# carrier.net
KiCad netlist of a schematic drawn in Altium Designer
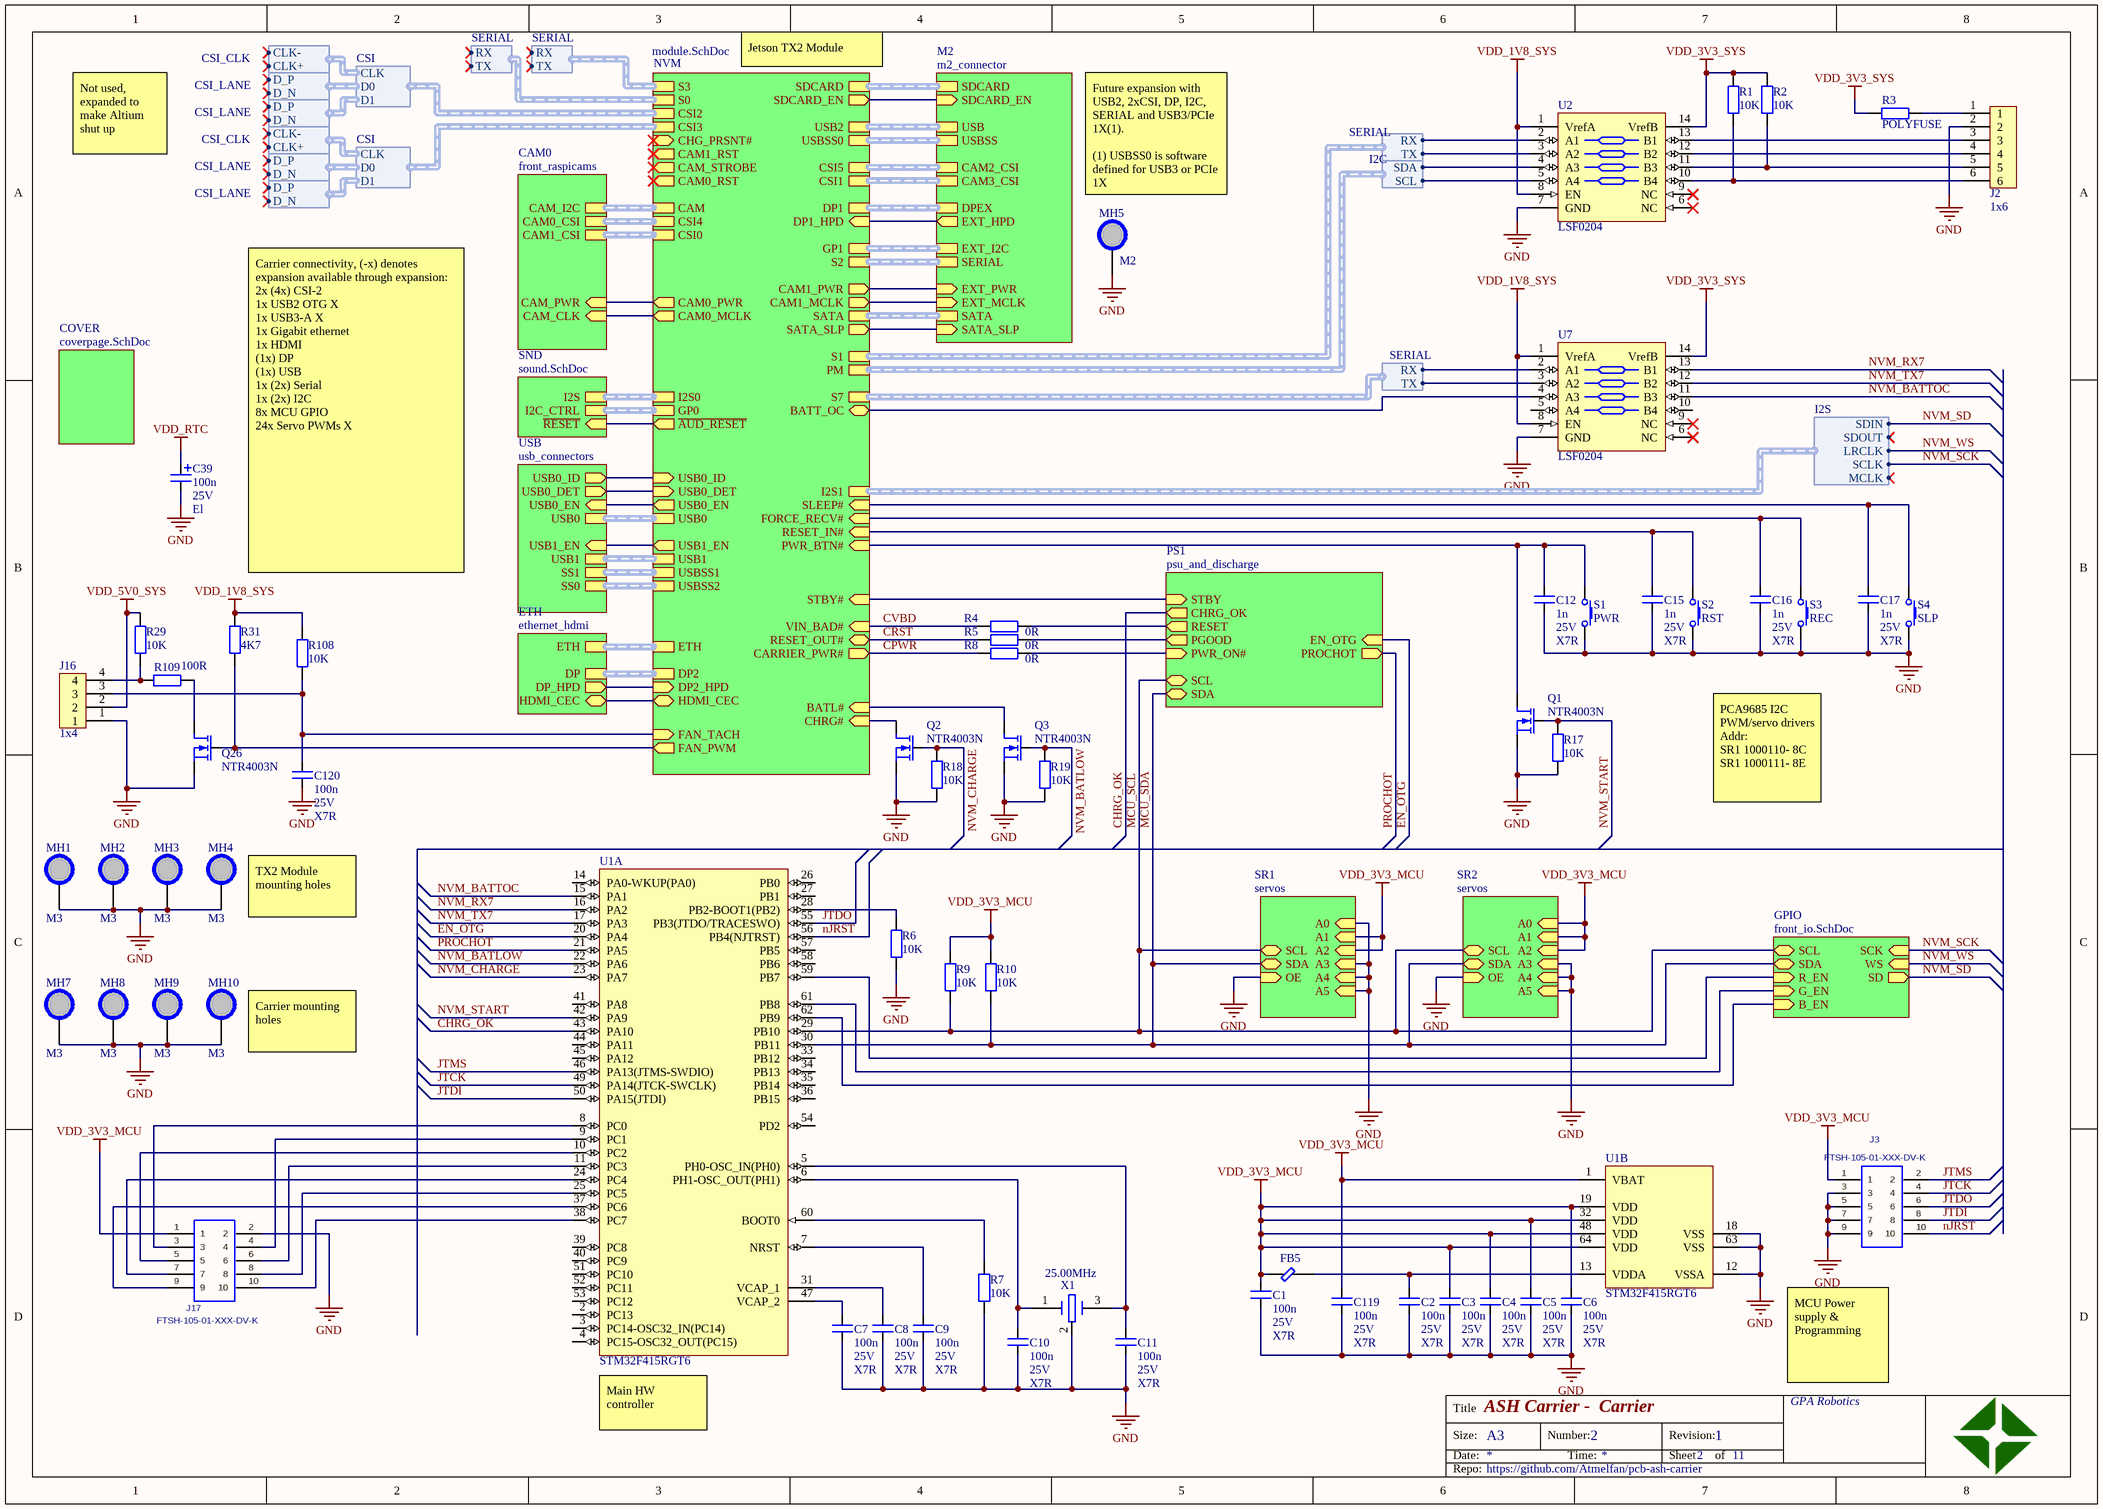
[diagram p0: carrier.SchDoc]

(export (version "E")
  (design (tool "Eeschema 10.0.6"))
  (components
    (comp (ref "C1")
      (value "100n")
      (footprint "C1005[0402]")
      (description "Capacitor")
      (fields (field (name "VOLTAGE") "25V") (field (name "TYPE") "X7R") (field (name "Comment") "cap"))
      (libsource (lib "gpa_passives") (part "cap"))
    )
    (comp (ref "C2")
      (value "100n")
      (footprint "C1005[0402]")
      (description "Capacitor")
      (fields (field (name "VOLTAGE") "25V") (field (name "TYPE") "X7R") (field (name "Comment") "cap"))
      (libsource (lib "gpa_passives") (part "cap"))
    )
    (comp (ref "C3")
      (value "100n")
      (footprint "C1005[0402]")
      (description "Capacitor")
      (fields (field (name "VOLTAGE") "25V") (field (name "TYPE") "X7R") (field (name "Comment") "cap"))
      (libsource (lib "gpa_passives") (part "cap"))
    )
    (comp (ref "C4")
      (value "100n")
      (footprint "C1005[0402]")
      (description "Capacitor")
      (fields (field (name "VOLTAGE") "25V") (field (name "TYPE") "X7R") (field (name "Comment") "cap"))
      (libsource (lib "gpa_passives") (part "cap"))
    )
    (comp (ref "C5")
      (value "100n")
      (footprint "C1005[0402]")
      (description "Capacitor")
      (fields (field (name "VOLTAGE") "25V") (field (name "TYPE") "X7R") (field (name "Comment") "cap"))
      (libsource (lib "gpa_passives") (part "cap"))
    )
    (comp (ref "C6")
      (value "100n")
      (footprint "C1005[0402]")
      (description "Capacitor")
      (fields (field (name "VOLTAGE") "25V") (field (name "TYPE") "X7R") (field (name "Comment") "cap"))
      (libsource (lib "gpa_passives") (part "cap"))
    )
    (comp (ref "C7")
      (value "100n")
      (footprint "C1005[0402]")
      (description "Capacitor")
      (fields (field (name "VOLTAGE") "25V") (field (name "TYPE") "X7R") (field (name "Comment") "cap"))
      (libsource (lib "gpa_passives") (part "cap"))
    )
    (comp (ref "C8")
      (value "100n")
      (footprint "C1005[0402]")
      (description "Capacitor")
      (fields (field (name "VOLTAGE") "25V") (field (name "TYPE") "X7R") (field (name "Comment") "cap"))
      (libsource (lib "gpa_passives") (part "cap"))
    )
    (comp (ref "C9")
      (value "100n")
      (footprint "C1005[0402]")
      (description "Capacitor")
      (fields (field (name "VOLTAGE") "25V") (field (name "TYPE") "X7R") (field (name "Comment") "cap"))
      (libsource (lib "gpa_passives") (part "cap"))
    )
    (comp (ref "C10")
      (value "100n")
      (footprint "C1005[0402]")
      (description "Capacitor")
      (fields (field (name "VOLTAGE") "25V") (field (name "TYPE") "X7R") (field (name "Comment") "cap"))
      (libsource (lib "gpa_passives") (part "cap"))
    )
    (comp (ref "C11")
      (value "100n")
      (footprint "C1005[0402]")
      (description "Capacitor")
      (fields (field (name "VOLTAGE") "25V") (field (name "TYPE") "X7R") (field (name "Comment") "cap"))
      (libsource (lib "gpa_passives") (part "cap"))
    )
    (comp (ref "C12")
      (value "1n")
      (footprint "C1005[0402]")
      (description "Capacitor")
      (fields (field (name "VOLTAGE") "25V") (field (name "TYPE") "X7R") (field (name "Comment") "cap"))
      (libsource (lib "gpa_passives") (part "cap"))
    )
    (comp (ref "C15")
      (value "1n")
      (footprint "C1005[0402]")
      (description "Capacitor")
      (fields (field (name "VOLTAGE") "25V") (field (name "TYPE") "X7R") (field (name "Comment") "cap"))
      (libsource (lib "gpa_passives") (part "cap"))
    )
    (comp (ref "C16")
      (value "1n")
      (footprint "C1005[0402]")
      (description "Capacitor")
      (fields (field (name "VOLTAGE") "25V") (field (name "TYPE") "X7R") (field (name "Comment") "cap"))
      (libsource (lib "gpa_passives") (part "cap"))
    )
    (comp (ref "C17")
      (value "1n")
      (footprint "C1005[0402]")
      (description "Capacitor")
      (fields (field (name "VOLTAGE") "25V") (field (name "TYPE") "X7R") (field (name "Comment") "cap"))
      (libsource (lib "gpa_passives") (part "cap"))
    )
    (comp (ref "C39")
      (value "100n")
      (footprint "SC_DSK-3R3H224U-HL")
      (description "Polarized capacitor")
      (fields (field (name "VOLTAGE") "25V") (field (name "TYPE") "El") (field (name "Comment") "pcap"))
      (libsource (lib "gpa_passives") (part "pcap"))
    )
    (comp (ref "C119")
      (value "100n")
      (footprint "C1005[0402]")
      (description "Capacitor")
      (fields (field (name "VOLTAGE") "25V") (field (name "TYPE") "X7R") (field (name "Comment") "cap"))
      (libsource (lib "gpa_passives") (part "cap"))
    )
    (comp (ref "C120")
      (value "100n")
      (footprint "C1005[0402]")
      (description "Capacitor")
      (fields (field (name "VOLTAGE") "25V") (field (name "TYPE") "X7R") (field (name "Comment") "cap"))
      (libsource (lib "gpa_passives") (part "cap"))
    )
    (comp (ref "FB5")
      (value "2506036007Y3")
      (footprint "FBC1608X07N")
      (description "Ferrite bead")
      (libsource (lib "gpa_passives") (part "ferrite_bead"))
    )
    (comp (ref "J2")
      (value "1x6")
      (footprint "hdr_100mil_1x6")
      (libsource (lib "gpa_connectors") (part "header_1x6"))
    )
    (comp (ref "J3")
      (value "FTSH-105-01-XXX-DV-K")
      (footprint "FTSH-105-01-XXX-DV-K")
      (description "TERMINAL STRIP, .050\"(1.27mm) PITCH, 10 PINS, KEYED")
      (fields (field (name "MANUFACTURER") "SAMTEC") (field (name "CREATED") "November 30, 2016 - Wendy Xin"))
      (libsource (lib "FTSH-105-01-XXX-DV-K") (part "FTSH-105-01-XXX-DV-K"))
    )
    (comp (ref "J16")
      (value "1x4")
      (footprint "molex_picoblade_1x4")
      (libsource (lib "gpa_connectors") (part "header_1x4"))
    )
    (comp (ref "J17")
      (value "FTSH-105-01-XXX-DV-K")
      (footprint "FTSH-105-01-XXX-DV-K")
      (description "TERMINAL STRIP, .050\"(1.27mm) PITCH, 10 PINS, KEYED")
      (fields (field (name "MANUFACTURER") "SAMTEC") (field (name "CREATED") "November 30, 2016 - Wendy Xin"))
      (libsource (lib "FTSH-105-01-XXX-DV-K") (part "FTSH-105-01-XXX-DV-K"))
    )
    (comp (ref "MH1")
      (value "M3")
      (footprint "m3_pan_tight_round")
      (libsource (lib "gpa_mounting") (part "mounting_hole"))
    )
    (comp (ref "MH2")
      (value "M3")
      (footprint "m3_pan_tight_round")
      (libsource (lib "gpa_mounting") (part "mounting_hole"))
    )
    (comp (ref "MH3")
      (value "M3")
      (footprint "m3_pan_tight_round")
      (libsource (lib "gpa_mounting") (part "mounting_hole"))
    )
    (comp (ref "MH4")
      (value "M3")
      (footprint "m3_pan_tight_round")
      (libsource (lib "gpa_mounting") (part "mounting_hole"))
    )
    (comp (ref "MH5")
      (value "M2")
      (footprint "m2_pan_tight_round")
      (libsource (lib "gpa_mounting") (part "mounting_hole"))
    )
    (comp (ref "MH7")
      (value "M3")
      (footprint "m3_pan_tight_round")
      (libsource (lib "gpa_mounting") (part "mounting_hole"))
    )
    (comp (ref "MH8")
      (value "M3")
      (footprint "m3_pan_tight_round")
      (libsource (lib "gpa_mounting") (part "mounting_hole"))
    )
    (comp (ref "MH9")
      (value "M3")
      (footprint "m3_pan_tight_round")
      (libsource (lib "gpa_mounting") (part "mounting_hole"))
    )
    (comp (ref "MH10")
      (value "M3")
      (footprint "m3_pan_tight_round")
      (libsource (lib "gpa_mounting") (part "mounting_hole"))
    )
    (comp (ref "Q1")
      (value "NTR4003N")
      (footprint "NCH_SOT95P237X110-3N")
      (libsource (lib "gpa_actives") (part "nch_mosfet"))
    )
    (comp (ref "Q2")
      (value "NTR4003N")
      (footprint "NCH_SOT95P237X110-3N")
      (libsource (lib "gpa_actives") (part "nch_mosfet"))
    )
    (comp (ref "Q3")
      (value "NTR4003N")
      (footprint "NCH_SOT95P237X110-3N")
      (libsource (lib "gpa_actives") (part "nch_mosfet"))
    )
    (comp (ref "Q26")
      (value "NTR4003N")
      (footprint "NCH_SOT95P237X110-3N")
      (libsource (lib "gpa_actives") (part "nch_mosfet"))
    )
    (comp (ref "R1")
      (value "10K")
      (footprint "R1005[0402]")
      (description "Resistor")
      (fields (field (name "Comment") "res"))
      (libsource (lib "") (part "res_1"))
    )
    (comp (ref "R2")
      (value "10K")
      (footprint "R1005[0402]")
      (description "Resistor")
      (fields (field (name "Comment") "res"))
      (libsource (lib "") (part "res_1"))
    )
    (comp (ref "R3")
      (value "POLYFUSE")
      (footprint "R1005[0402]")
      (description "Resistor")
      (fields (field (name "Comment") "res"))
      (libsource (lib "gpa_passives") (part "res"))
    )
    (comp (ref "R4")
      (value "0R")
      (footprint "R1005[0402]")
      (description "Resistor")
      (fields (field (name "Comment") "res"))
      (libsource (lib "") (part "res_1"))
    )
    (comp (ref "R5")
      (value "0R")
      (footprint "R1005[0402]")
      (description "Resistor")
      (fields (field (name "Comment") "res"))
      (libsource (lib "") (part "res_1"))
    )
    (comp (ref "R6")
      (value "10K")
      (footprint "R1005[0402]")
      (description "Resistor")
      (fields (field (name "Comment") "res"))
      (libsource (lib "") (part "res_2"))
    )
    (comp (ref "R7")
      (value "10K")
      (footprint "R1005[0402]")
      (description "Resistor")
      (fields (field (name "Comment") "res"))
      (libsource (lib "") (part "res_2"))
    )
    (comp (ref "R8")
      (value "0R")
      (footprint "R1005[0402]")
      (description "Resistor")
      (fields (field (name "Comment") "res"))
      (libsource (lib "") (part "res_1"))
    )
    (comp (ref "R9")
      (value "10K")
      (footprint "R1005[0402]")
      (description "Resistor")
      (fields (field (name "Comment") "res"))
      (libsource (lib "") (part "res_2"))
    )
    (comp (ref "R10")
      (value "10K")
      (footprint "R1005[0402]")
      (description "Resistor")
      (fields (field (name "Comment") "res"))
      (libsource (lib "") (part "res_2"))
    )
    (comp (ref "R17")
      (value "10K")
      (footprint "R1005[0402]")
      (description "Resistor")
      (fields (field (name "Comment") "res"))
      (libsource (lib "") (part "res_2"))
    )
    (comp (ref "R18")
      (value "10K")
      (footprint "R1005[0402]")
      (description "Resistor")
      (fields (field (name "Comment") "res"))
      (libsource (lib "") (part "res_2"))
    )
    (comp (ref "R19")
      (value "10K")
      (footprint "R1005[0402]")
      (description "Resistor")
      (fields (field (name "Comment") "res"))
      (libsource (lib "") (part "res_2"))
    )
    (comp (ref "R29")
      (value "10K")
      (footprint "R1005[0402]")
      (description "Resistor")
      (fields (field (name "TOLERANCE") "5%") (field (name "Comment") "res"))
      (libsource (lib "gpa_passives") (part "res"))
    )
    (comp (ref "R31")
      (value "4K7")
      (footprint "R1005[0402]")
      (description "Resistor")
      (fields (field (name "TOLERANCE") "5%") (field (name "Comment") "res"))
      (libsource (lib "") (part "res_2"))
    )
    (comp (ref "R108")
      (value "10K")
      (footprint "R1005[0402]")
      (description "Resistor")
      (fields (field (name "TOLERANCE") "5%") (field (name "Comment") "res"))
      (libsource (lib "") (part "res_2"))
    )
    (comp (ref "R109")
      (value "100R")
      (footprint "R1005[0402]")
      (description "Resistor")
      (fields (field (name "TOLERANCE") "5%") (field (name "Comment") "res"))
      (libsource (lib "") (part "res_1"))
    )
    (comp (ref "S1")
      (value "PWR")
      (footprint "SW_6MM_TACT")
      (fields (field (name "TEXT") "PWR"))
      (libsource (lib "gpa_passives") (part "btn"))
    )
    (comp (ref "S2")
      (value "RST")
      (footprint "SW_6MM_TACT")
      (fields (field (name "TEXT") "RST"))
      (libsource (lib "gpa_passives") (part "btn"))
    )
    (comp (ref "S3")
      (value "REC")
      (footprint "SW_6MM_TACT")
      (fields (field (name "TEXT") "REC"))
      (libsource (lib "gpa_passives") (part "btn"))
    )
    (comp (ref "S4")
      (value "SLP")
      (footprint "SW_6MM_TACT")
      (fields (field (name "TEXT") "SLP"))
      (libsource (lib "gpa_passives") (part "btn"))
    )
    (comp (ref "U1")
      (value "STM32F415RGT6")
      (footprint "STM-LQFP64_N")
      (fields (field (name "MANUFACTURER") "STMicroelectronics"))
      (libsource (lib "STMicroelectronics STM32 F4") (part "STM32F415RGT6"))
    )
    (comp (ref "U2")
      (value "LSF0204")
      (footprint "TI_TSOP65P640X120-14N")
      (libsource (lib "gpa_ti") (part "lsf0204"))
    )
    (comp (ref "U7")
      (value "LSF0204")
      (footprint "TI_TSOP65P640X120-14N")
      (libsource (lib "gpa_ti") (part "lsf0204"))
    )
    (comp (ref "X1")
      (value "25.00MHz")
      (footprint "FA-238")
      (description "Crystal with shield")
      (fields (field (name "Comment") "crystal_shielded"))
      (libsource (lib "gpa_passives") (part "crystal_shielded"))
    )
  )
  (nets
    (net (code "6") (name "/BATL#") (class "Default")
      (node (ref "Q3") (pin "D") (pinfunction "D_D") (pintype "passive"))
    )
    (net (code "7") (name "/BATT_OC") (class "Default")
      (node (ref "U7") (pin "4") (pinfunction "A3_4") (pintype "bidirectional"))
    )
    (net (code "8") (name "/B_EN") (class "Default")
      (node (ref "U1") (pin "62") (pinfunction "PB9_62") (pintype "bidirectional"))
    )
    (net (code "22") (name "/CHRG#") (class "Default")
      (node (ref "Q2") (pin "D") (pinfunction "D_D") (pintype "passive"))
    )
    (net (code "23") (name "/CHRG_OK") (class "Default")
      (node (ref "U1") (pin "43") (pinfunction "PA10_43") (pintype "bidirectional"))
    )
    (net (code "24") (name "/CPWR") (class "Default")
      (node (ref "R8") (pin "1") (pinfunction "1_1") (pintype "passive"))
    )
    (net (code "25") (name "/CRST") (class "Default")
      (node (ref "R5") (pin "1") (pinfunction "1_1") (pintype "passive"))
    )
    (net (code "27") (name "/CVBD") (class "Default")
      (node (ref "R4") (pin "1") (pinfunction "1_1") (pintype "passive"))
    )
    (net (code "31") (name "/EN_OTG") (class "Default")
      (node (ref "U1") (pin "20") (pinfunction "PA4_20") (pintype "bidirectional"))
    )
    (net (code "35") (name "/FAN_PWM") (class "Default")
      (node (ref "Q26") (pin "G") (pinfunction "G_G") (pintype "passive"))
      (node (ref "R31") (pin "1") (pinfunction "1_1") (pintype "passive"))
    )
    (net (code "36") (name "/FAN_TACH") (class "Default")
      (node (ref "C120") (pin "2") (pinfunction "2_2") (pintype "passive"))
      (node (ref "J16") (pin "3") (pinfunction "3_3") (pintype "passive"))
      (node (ref "R108") (pin "1") (pinfunction "1_1") (pintype "passive"))
    )
    (net (code "37") (name "/FORCE_RECV#") (class "Default")
      (node (ref "C16") (pin "2") (pinfunction "2_2") (pintype "passive"))
      (node (ref "S3") (pin "1") (pinfunction "1_1") (pintype "passive"))
    )
    (net (code "39") (name "/G_EN") (class "Default")
      (node (ref "U1") (pin "61") (pinfunction "PB8_61") (pintype "bidirectional"))
    )
    (net (code "42") (name "/JTCK") (class "Default")
      (node (ref "J3") (pin "4") (pinfunction "4_4") (pintype "passive"))
      (node (ref "U1") (pin "49") (pinfunction "PA14(JTCK-SWCLK)_49") (pintype "bidirectional"))
    )
    (net (code "43") (name "/JTDI") (class "Default")
      (node (ref "J3") (pin "8") (pinfunction "8_8") (pintype "passive"))
      (node (ref "U1") (pin "50") (pinfunction "PA15(JTDI)_50") (pintype "bidirectional"))
    )
    (net (code "44") (name "/JTDO") (class "Default")
      (node (ref "J3") (pin "6") (pinfunction "6_6") (pintype "passive"))
      (node (ref "U1") (pin "55") (pinfunction "PB3(JTDO/TRACESWO)_55") (pintype "bidirectional"))
    )
    (net (code "45") (name "/JTMS") (class "Default")
      (node (ref "J3") (pin "2") (pinfunction "2_2") (pintype "passive"))
      (node (ref "U1") (pin "46") (pinfunction "PA13(JTMS-SWDIO)_46") (pintype "bidirectional"))
    )
    (net (code "46") (name "/MCU_SCL") (class "Default")
      (node (ref "R9") (pin "1") (pinfunction "1_1") (pintype "passive"))
      (node (ref "U1") (pin "29") (pinfunction "PB10_29") (pintype "bidirectional"))
    )
    (net (code "47") (name "/MCU_SDA") (class "Default")
      (node (ref "R10") (pin "1") (pinfunction "1_1") (pintype "passive"))
      (node (ref "U1") (pin "30") (pinfunction "PB11_30") (pintype "bidirectional"))
    )
    (net (code "48") (name "/NVM_BATLOW") (class "Default")
      (node (ref "Q3") (pin "G") (pinfunction "G_G") (pintype "passive"))
      (node (ref "R19") (pin "2") (pinfunction "2_2") (pintype "passive"))
      (node (ref "U1") (pin "22") (pinfunction "PA6_22") (pintype "bidirectional"))
    )
    (net (code "49") (name "/NVM_BATTOC") (class "Default")
      (node (ref "U1") (pin "15") (pinfunction "PA1_15") (pintype "bidirectional"))
      (node (ref "U7") (pin "11") (pinfunction "B3_11") (pintype "bidirectional"))
    )
    (net (code "50") (name "/NVM_CHARGE") (class "Default")
      (node (ref "Q2") (pin "G") (pinfunction "G_G") (pintype "passive"))
      (node (ref "R18") (pin "2") (pinfunction "2_2") (pintype "passive"))
      (node (ref "U1") (pin "23") (pinfunction "PA7_23") (pintype "bidirectional"))
    )
    (net (code "51") (name "/NVM_RX7") (class "Default")
      (node (ref "U1") (pin "16") (pinfunction "PA2_16") (pintype "bidirectional"))
      (node (ref "U7") (pin "13") (pinfunction "B1_13") (pintype "bidirectional"))
    )
    (net (code "54") (name "/NVM_START") (class "Default")
      (node (ref "Q1") (pin "G") (pinfunction "G_G") (pintype "passive"))
      (node (ref "R17") (pin "2") (pinfunction "2_2") (pintype "passive"))
      (node (ref "U1") (pin "42") (pinfunction "PA9_42") (pintype "bidirectional"))
    )
    (net (code "55") (name "/NVM_TX7") (class "Default")
      (node (ref "U1") (pin "17") (pinfunction "PA3_17") (pintype "bidirectional"))
      (node (ref "U7") (pin "12") (pinfunction "B2_12") (pintype "bidirectional"))
    )
    (net (code "57") (name "/PGOOD") (class "Default")
      (node (ref "R5") (pin "2") (pinfunction "2_2") (pintype "passive"))
    )
    (net (code "58") (name "/PROCHOT") (class "Default")
      (node (ref "U1") (pin "21") (pinfunction "PA5_21") (pintype "bidirectional"))
    )
    (net (code "59") (name "/PWR_BTN#") (class "Default")
      (node (ref "C12") (pin "2") (pinfunction "2_2") (pintype "passive"))
      (node (ref "Q1") (pin "D") (pinfunction "D_D") (pintype "passive"))
      (node (ref "S1") (pin "1") (pinfunction "1_1") (pintype "passive"))
    )
    (net (code "60") (name "/PWR_ON#") (class "Default")
      (node (ref "R8") (pin "2") (pinfunction "2_2") (pintype "passive"))
    )
    (net (code "61") (name "/RESET") (class "Default")
      (node (ref "R4") (pin "2") (pinfunction "2_2") (pintype "passive"))
    )
    (net (code "62") (name "/RESET_IN#") (class "Default")
      (node (ref "C15") (pin "2") (pinfunction "2_2") (pintype "passive"))
      (node (ref "S2") (pin "1") (pinfunction "1_1") (pintype "passive"))
    )
    (net (code "63") (name "/R_EN") (class "Default")
      (node (ref "U1") (pin "59") (pinfunction "PB7_59") (pintype "bidirectional"))
    )
    (net (code "70") (name "/SLEEP#") (class "Default")
      (node (ref "C17") (pin "2") (pinfunction "2_2") (pintype "passive"))
      (node (ref "S4") (pin "1") (pinfunction "1_1") (pintype "passive"))
    )
    (net (code "82") (name "/nJRST") (class "Default")
      (node (ref "J3") (pin "10") (pinfunction "10_10") (pintype "passive"))
      (node (ref "U1") (pin "56") (pinfunction "PB4(NJTRST)_56") (pintype "bidirectional"))
    )
    (net (code "87") (name "GND") (class "Default")
      (node (ref "C1") (pin "2") (pinfunction "2_2") (pintype "passive"))
      (node (ref "C10") (pin "2") (pinfunction "2_2") (pintype "passive"))
      (node (ref "C11") (pin "2") (pinfunction "2_2") (pintype "passive"))
      (node (ref "C119") (pin "2") (pinfunction "2_2") (pintype "passive"))
      (node (ref "C12") (pin "1") (pinfunction "1_1") (pintype "passive"))
      (node (ref "C120") (pin "1") (pinfunction "1_1") (pintype "passive"))
      (node (ref "C15") (pin "1") (pinfunction "1_1") (pintype "passive"))
      (node (ref "C16") (pin "1") (pinfunction "1_1") (pintype "passive"))
      (node (ref "C17") (pin "1") (pinfunction "1_1") (pintype "passive"))
      (node (ref "C2") (pin "2") (pinfunction "2_2") (pintype "passive"))
      (node (ref "C3") (pin "2") (pinfunction "2_2") (pintype "passive"))
      (node (ref "C39") (pin "2") (pinfunction "2_2") (pintype "passive"))
      (node (ref "C4") (pin "2") (pinfunction "2_2") (pintype "passive"))
      (node (ref "C5") (pin "2") (pinfunction "2_2") (pintype "passive"))
      (node (ref "C6") (pin "2") (pinfunction "2_2") (pintype "passive"))
      (node (ref "C7") (pin "2") (pinfunction "2_2") (pintype "passive"))
      (node (ref "C8") (pin "2") (pinfunction "2_2") (pintype "passive"))
      (node (ref "C9") (pin "2") (pinfunction "2_2") (pintype "passive"))
      (node (ref "J16") (pin "1") (pinfunction "1_1") (pintype "passive"))
      (node (ref "J17") (pin "2") (pinfunction "2_2") (pintype "passive"))
      (node (ref "J2") (pin "2") (pinfunction "2_2") (pintype "passive"))
      (node (ref "J3") (pin "3") (pinfunction "3_3") (pintype "passive"))
      (node (ref "J3") (pin "5") (pinfunction "5_5") (pintype "passive"))
      (node (ref "J3") (pin "7") (pinfunction "7_7") (pintype "passive"))
      (node (ref "J3") (pin "9") (pinfunction "9_9") (pintype "passive"))
      (node (ref "MH1") (pin "1") (pinfunction "1_1") (pintype "passive"))
      (node (ref "MH10") (pin "1") (pinfunction "1_1") (pintype "passive"))
      (node (ref "MH2") (pin "1") (pinfunction "1_1") (pintype "passive"))
      (node (ref "MH3") (pin "1") (pinfunction "1_1") (pintype "passive"))
      (node (ref "MH4") (pin "1") (pinfunction "1_1") (pintype "passive"))
      (node (ref "MH5") (pin "1") (pinfunction "1_1") (pintype "passive"))
      (node (ref "MH7") (pin "1") (pinfunction "1_1") (pintype "passive"))
      (node (ref "MH8") (pin "1") (pinfunction "1_1") (pintype "passive"))
      (node (ref "MH9") (pin "1") (pinfunction "1_1") (pintype "passive"))
      (node (ref "Q1") (pin "S") (pinfunction "S_S") (pintype "passive"))
      (node (ref "Q2") (pin "S") (pinfunction "S_S") (pintype "passive"))
      (node (ref "Q26") (pin "S") (pinfunction "S_S") (pintype "passive"))
      (node (ref "Q3") (pin "S") (pinfunction "S_S") (pintype "passive"))
      (node (ref "R17") (pin "1") (pinfunction "1_1") (pintype "passive"))
      (node (ref "R18") (pin "1") (pinfunction "1_1") (pintype "passive"))
      (node (ref "R19") (pin "1") (pinfunction "1_1") (pintype "passive"))
      (node (ref "R6") (pin "1") (pinfunction "1_1") (pintype "passive"))
      (node (ref "R7") (pin "1") (pinfunction "1_1") (pintype "passive"))
      (node (ref "S1") (pin "2") (pinfunction "2_2") (pintype "passive"))
      (node (ref "S2") (pin "2") (pinfunction "2_2") (pintype "passive"))
      (node (ref "S3") (pin "2") (pinfunction "2_2") (pintype "passive"))
      (node (ref "S4") (pin "2") (pinfunction "2_2") (pintype "passive"))
      (node (ref "U1") (pin "12") (pinfunction "VSSA_12") (pintype "power_in"))
      (node (ref "U1") (pin "18") (pinfunction "VSS_18") (pintype "power_in"))
      (node (ref "U1") (pin "63") (pinfunction "VSS_63") (pintype "power_in"))
      (node (ref "U2") (pin "7") (pinfunction "GND_7") (pintype "power_in"))
      (node (ref "U7") (pin "7") (pinfunction "GND_7") (pintype "power_in"))
      (node (ref "X1") (pin "2") (pinfunction "2_2") (pintype "passive"))
    )
    (net (code "88") (name "Net-(J2-Pad1)") (class "Default")
      (node (ref "J2") (pin "1") (pinfunction "1_1") (pintype "passive"))
      (node (ref "R3") (pin "1") (pinfunction "1_1") (pintype "passive"))
    )
    (net (code "89") (name "Net-(J16-Pad4)") (class "Default")
      (node (ref "J16") (pin "4") (pinfunction "4_4") (pintype "passive"))
      (node (ref "R109") (pin "1") (pinfunction "1_1") (pintype "passive"))
      (node (ref "R29") (pin "2") (pinfunction "2_2") (pintype "passive"))
    )
    (net (code "90") (name "Net-(Q26-PadD)") (class "Default")
      (node (ref "Q26") (pin "D") (pinfunction "D_D") (pintype "passive"))
      (node (ref "R109") (pin "2") (pinfunction "2_2") (pintype "passive"))
    )
    (net (code "91") (name "Net-(U1A-BOOT0)") (class "Default")
      (node (ref "R7") (pin "2") (pinfunction "2_2") (pintype "passive"))
      (node (ref "U1") (pin "60") (pinfunction "BOOT0_60") (pintype "input"))
    )
    (net (code "92") (name "Net-(U1A-NRST)") (class "Default")
      (node (ref "C9") (pin "1") (pinfunction "1_1") (pintype "passive"))
      (node (ref "U1") (pin "7") (pinfunction "NRST_7") (pintype "bidirectional"))
    )
    (net (code "93") (name "Net-(U1A-PB2-BOOT1(PB2))") (class "Default")
      (node (ref "R6") (pin "2") (pinfunction "2_2") (pintype "passive"))
      (node (ref "U1") (pin "28") (pinfunction "PB2-BOOT1(PB2)_28") (pintype "bidirectional"))
    )
    (net (code "94") (name "Net-(U1A-PC0)") (class "Default")
      (node (ref "J17") (pin "3") (pinfunction "3_3") (pintype "passive"))
      (node (ref "U1") (pin "8") (pinfunction "PC0_8") (pintype "bidirectional"))
    )
    (net (code "95") (name "Net-(U1A-PC1)") (class "Default")
      (node (ref "J17") (pin "4") (pinfunction "4_4") (pintype "passive"))
      (node (ref "U1") (pin "9") (pinfunction "PC1_9") (pintype "bidirectional"))
    )
    (net (code "96") (name "Net-(U1A-PC2)") (class "Default")
      (node (ref "J17") (pin "5") (pinfunction "5_5") (pintype "passive"))
      (node (ref "U1") (pin "10") (pinfunction "PC2_10") (pintype "bidirectional"))
    )
    (net (code "97") (name "Net-(U1A-PC3)") (class "Default")
      (node (ref "J17") (pin "6") (pinfunction "6_6") (pintype "passive"))
      (node (ref "U1") (pin "11") (pinfunction "PC3_11") (pintype "bidirectional"))
    )
    (net (code "98") (name "Net-(U1A-PC4)") (class "Default")
      (node (ref "J17") (pin "7") (pinfunction "7_7") (pintype "passive"))
      (node (ref "U1") (pin "24") (pinfunction "PC4_24") (pintype "bidirectional"))
    )
    (net (code "99") (name "Net-(U1A-PC5)") (class "Default")
      (node (ref "J17") (pin "8") (pinfunction "8_8") (pintype "passive"))
      (node (ref "U1") (pin "25") (pinfunction "PC5_25") (pintype "bidirectional"))
    )
    (net (code "100") (name "Net-(U1A-PC6)") (class "Default")
      (node (ref "J17") (pin "9") (pinfunction "9_9") (pintype "passive"))
      (node (ref "U1") (pin "37") (pinfunction "PC6_37") (pintype "bidirectional"))
    )
    (net (code "101") (name "Net-(U1A-PC7)") (class "Default")
      (node (ref "J17") (pin "10") (pinfunction "10_10") (pintype "passive"))
      (node (ref "U1") (pin "38") (pinfunction "PC7_38") (pintype "bidirectional"))
    )
    (net (code "102") (name "Net-(U1A-PH0-OSC_IN(PH0))") (class "Default")
      (node (ref "C11") (pin "1") (pinfunction "1_1") (pintype "passive"))
      (node (ref "U1") (pin "5") (pinfunction "PH0-OSC_IN(PH0)_5") (pintype "bidirectional"))
      (node (ref "X1") (pin "3") (pinfunction "3_3") (pintype "passive"))
    )
    (net (code "103") (name "Net-(U1A-PH1-OSC_OUT(PH1))") (class "Default")
      (node (ref "C10") (pin "1") (pinfunction "1_1") (pintype "passive"))
      (node (ref "U1") (pin "6") (pinfunction "PH1-OSC_OUT(PH1)_6") (pintype "bidirectional"))
      (node (ref "X1") (pin "1") (pinfunction "1_1") (pintype "passive"))
    )
    (net (code "104") (name "Net-(U1A-VCAP_1)") (class "Default")
      (node (ref "C8") (pin "1") (pinfunction "1_1") (pintype "passive"))
      (node (ref "U1") (pin "31") (pinfunction "VCAP_1_31") (pintype "power_in"))
    )
    (net (code "105") (name "Net-(U1A-VCAP_2)") (class "Default")
      (node (ref "C7") (pin "1") (pinfunction "1_1") (pintype "passive"))
      (node (ref "U1") (pin "47") (pinfunction "VCAP_2_47") (pintype "power_in"))
    )
    (net (code "106") (name "Net-(U1B-VDDA)") (class "Default")
      (node (ref "C2") (pin "1") (pinfunction "1_1") (pintype "passive"))
      (node (ref "FB5") (pin "2") (pinfunction "2_2") (pintype "passive"))
      (node (ref "U1") (pin "13") (pinfunction "VDDA_13") (pintype "power_in"))
    )
    (net (code "107") (name "Net-(U2-B1)") (class "Default")
      (node (ref "J2") (pin "3") (pinfunction "3_3") (pintype "passive"))
      (node (ref "U2") (pin "13") (pinfunction "B1_13") (pintype "bidirectional"))
    )
    (net (code "108") (name "Net-(U2-B2)") (class "Default")
      (node (ref "J2") (pin "4") (pinfunction "4_4") (pintype "passive"))
      (node (ref "U2") (pin "12") (pinfunction "B2_12") (pintype "bidirectional"))
    )
    (net (code "109") (name "Net-(U2-B3)") (class "Default")
      (node (ref "J2") (pin "5") (pinfunction "5_5") (pintype "passive"))
      (node (ref "R2") (pin "1") (pinfunction "1_1") (pintype "passive"))
      (node (ref "U2") (pin "11") (pinfunction "B3_11") (pintype "bidirectional"))
    )
    (net (code "110") (name "Net-(U2-B4)") (class "Default")
      (node (ref "J2") (pin "6") (pinfunction "6_6") (pintype "passive"))
      (node (ref "R1") (pin "1") (pinfunction "1_1") (pintype "passive"))
      (node (ref "U2") (pin "10") (pinfunction "B4_10") (pintype "bidirectional"))
    )
    (net (code "111") (name "VDD_1V8_SYS") (class "Default")
      (node (ref "R108") (pin "2") (pinfunction "2_2") (pintype "passive"))
      (node (ref "R31") (pin "2") (pinfunction "2_2") (pintype "passive"))
      (node (ref "U2") (pin "1") (pinfunction "VrefA_1") (pintype "power_in"))
      (node (ref "U2") (pin "8") (pinfunction "EN_8") (pintype "input"))
      (node (ref "U7") (pin "1") (pinfunction "VrefA_1") (pintype "power_in"))
      (node (ref "U7") (pin "8") (pinfunction "EN_8") (pintype "input"))
    )
    (net (code "112") (name "VDD_3V3_MCU") (class "Default")
      (node (ref "C1") (pin "1") (pinfunction "1_1") (pintype "passive"))
      (node (ref "C119") (pin "1") (pinfunction "1_1") (pintype "passive"))
      (node (ref "C3") (pin "1") (pinfunction "1_1") (pintype "passive"))
      (node (ref "C4") (pin "1") (pinfunction "1_1") (pintype "passive"))
      (node (ref "C5") (pin "1") (pinfunction "1_1") (pintype "passive"))
      (node (ref "C6") (pin "1") (pinfunction "1_1") (pintype "passive"))
      (node (ref "FB5") (pin "1") (pinfunction "1_1") (pintype "passive"))
      (node (ref "J17") (pin "1") (pinfunction "1_1") (pintype "passive"))
      (node (ref "J3") (pin "1") (pinfunction "1_1") (pintype "passive"))
      (node (ref "R10") (pin "2") (pinfunction "2_2") (pintype "passive"))
      (node (ref "R9") (pin "2") (pinfunction "2_2") (pintype "passive"))
      (node (ref "U1") (pin "1") (pinfunction "VBAT_1") (pintype "power_in"))
      (node (ref "U1") (pin "19") (pinfunction "VDD_19") (pintype "power_in"))
      (node (ref "U1") (pin "32") (pinfunction "VDD_32") (pintype "power_in"))
      (node (ref "U1") (pin "48") (pinfunction "VDD_48") (pintype "power_in"))
      (node (ref "U1") (pin "64") (pinfunction "VDD_64") (pintype "power_in"))
    )
    (net (code "113") (name "VDD_3V3_SYS") (class "Default")
      (node (ref "R1") (pin "2") (pinfunction "2_2") (pintype "passive"))
      (node (ref "R2") (pin "2") (pinfunction "2_2") (pintype "passive"))
      (node (ref "R3") (pin "2") (pinfunction "2_2") (pintype "passive"))
      (node (ref "U2") (pin "14") (pinfunction "VrefB_14") (pintype "power_in"))
      (node (ref "U7") (pin "14") (pinfunction "VrefB_14") (pintype "power_in"))
    )
    (net (code "114") (name "VDD_5V0_SYS") (class "Default")
      (node (ref "J16") (pin "2") (pinfunction "2_2") (pintype "passive"))
      (node (ref "R29") (pin "1") (pinfunction "1_1") (pintype "passive"))
    )
    (net (code "115") (name "VDD_RTC") (class "Default")
      (node (ref "C39") (pin "1") (pinfunction "1_1") (pintype "passive"))
    )
    (net (code "116") (name "unconnected-(U1A-PA0-WKUP(PA0)-Pad14)") (class "Default")
      (node (ref "U1") (pin "14") (pinfunction "PA0-WKUP(PA0)_14") (pintype "bidirectional"))
    )
    (net (code "117") (name "unconnected-(U1A-PA8-Pad41)") (class "Default")
      (node (ref "U1") (pin "41") (pinfunction "PA8_41") (pintype "bidirectional"))
    )
    (net (code "118") (name "unconnected-(U1A-PA11-Pad44)") (class "Default")
      (node (ref "U1") (pin "44") (pinfunction "PA11_44") (pintype "bidirectional"))
    )
    (net (code "119") (name "unconnected-(U1A-PA12-Pad45)") (class "Default")
      (node (ref "U1") (pin "45") (pinfunction "PA12_45") (pintype "bidirectional"))
    )
    (net (code "120") (name "unconnected-(U1A-PB0-Pad26)") (class "Default")
      (node (ref "U1") (pin "26") (pinfunction "PB0_26") (pintype "bidirectional"))
    )
    (net (code "121") (name "unconnected-(U1A-PB1-Pad27)") (class "Default")
      (node (ref "U1") (pin "27") (pinfunction "PB1_27") (pintype "bidirectional"))
    )
    (net (code "122") (name "unconnected-(U1A-PB5-Pad57)") (class "Default")
      (node (ref "U1") (pin "57") (pinfunction "PB5_57") (pintype "bidirectional"))
    )
    (net (code "123") (name "unconnected-(U1A-PB6-Pad58)") (class "Default")
      (node (ref "U1") (pin "58") (pinfunction "PB6_58") (pintype "bidirectional"))
    )
    (net (code "124") (name "unconnected-(U1A-PB12-Pad33)") (class "Default")
      (node (ref "U1") (pin "33") (pinfunction "PB12_33") (pintype "bidirectional"))
    )
    (net (code "125") (name "unconnected-(U1A-PB13-Pad34)") (class "Default")
      (node (ref "U1") (pin "34") (pinfunction "PB13_34") (pintype "bidirectional"))
    )
    (net (code "126") (name "unconnected-(U1A-PB14-Pad35)") (class "Default")
      (node (ref "U1") (pin "35") (pinfunction "PB14_35") (pintype "bidirectional"))
    )
    (net (code "127") (name "unconnected-(U1A-PB15-Pad36)") (class "Default")
      (node (ref "U1") (pin "36") (pinfunction "PB15_36") (pintype "bidirectional"))
    )
    (net (code "128") (name "unconnected-(U1A-PC8-Pad39)") (class "Default")
      (node (ref "U1") (pin "39") (pinfunction "PC8_39") (pintype "bidirectional"))
    )
    (net (code "129") (name "unconnected-(U1A-PC9-Pad40)") (class "Default")
      (node (ref "U1") (pin "40") (pinfunction "PC9_40") (pintype "bidirectional"))
    )
    (net (code "130") (name "unconnected-(U1A-PC10-Pad51)") (class "Default")
      (node (ref "U1") (pin "51") (pinfunction "PC10_51") (pintype "bidirectional"))
    )
    (net (code "131") (name "unconnected-(U1A-PC11-Pad52)") (class "Default")
      (node (ref "U1") (pin "52") (pinfunction "PC11_52") (pintype "bidirectional"))
    )
    (net (code "132") (name "unconnected-(U1A-PC12-Pad53)") (class "Default")
      (node (ref "U1") (pin "53") (pinfunction "PC12_53") (pintype "bidirectional"))
    )
    (net (code "133") (name "unconnected-(U1A-PC13-Pad2)") (class "Default")
      (node (ref "U1") (pin "2") (pinfunction "PC13_2") (pintype "bidirectional"))
    )
    (net (code "134") (name "unconnected-(U1A-PC14-OSC32_IN(PC14)-Pad3)") (class "Default")
      (node (ref "U1") (pin "3") (pinfunction "PC14-OSC32_IN(PC14)_3") (pintype "bidirectional"))
    )
    (net (code "135") (name "unconnected-(U1A-PC15-OSC32_OUT(PC15)-Pad4)") (class "Default")
      (node (ref "U1") (pin "4") (pinfunction "PC15-OSC32_OUT(PC15)_4") (pintype "bidirectional"))
    )
    (net (code "136") (name "unconnected-(U1A-PD2-Pad54)") (class "Default")
      (node (ref "U1") (pin "54") (pinfunction "PD2_54") (pintype "bidirectional"))
    )
    (net (code "137") (name "unconnected-(U2-A1-Pad2)") (class "Default")
      (node (ref "U2") (pin "2") (pinfunction "A1_2") (pintype "bidirectional"))
    )
    (net (code "138") (name "unconnected-(U2-A2-Pad3)") (class "Default")
      (node (ref "U2") (pin "3") (pinfunction "A2_3") (pintype "bidirectional"))
    )
    (net (code "139") (name "unconnected-(U2-A3-Pad4)") (class "Default")
      (node (ref "U2") (pin "4") (pinfunction "A3_4") (pintype "bidirectional"))
    )
    (net (code "140") (name "unconnected-(U2-A4-Pad5)") (class "Default")
      (node (ref "U2") (pin "5") (pinfunction "A4_5") (pintype "bidirectional"))
    )
    (net (code "141") (name "unconnected-(U2-NC-Pad6)") (class "Default")
      (node (ref "U2") (pin "6") (pinfunction "NC_6") (pintype "input+no_connect"))
    )
    (net (code "142") (name "unconnected-(U2-NC-Pad9)") (class "Default")
      (node (ref "U2") (pin "9") (pinfunction "NC_9") (pintype "input+no_connect"))
    )
    (net (code "143") (name "unconnected-(U7-A1-Pad2)") (class "Default")
      (node (ref "U7") (pin "2") (pinfunction "A1_2") (pintype "bidirectional"))
    )
    (net (code "144") (name "unconnected-(U7-A2-Pad3)") (class "Default")
      (node (ref "U7") (pin "3") (pinfunction "A2_3") (pintype "bidirectional"))
    )
    (net (code "145") (name "unconnected-(U7-A4-Pad5)") (class "Default")
      (node (ref "U7") (pin "5") (pinfunction "A4_5") (pintype "bidirectional"))
    )
    (net (code "146") (name "unconnected-(U7-B4-Pad10)") (class "Default")
      (node (ref "U7") (pin "10") (pinfunction "B4_10") (pintype "bidirectional"))
    )
    (net (code "147") (name "unconnected-(U7-NC-Pad6)") (class "Default")
      (node (ref "U7") (pin "6") (pinfunction "NC_6") (pintype "input+no_connect"))
    )
    (net (code "148") (name "unconnected-(U7-NC-Pad9)") (class "Default")
      (node (ref "U7") (pin "9") (pinfunction "NC_9") (pintype "input+no_connect"))
    )
  )
)
